# Sensor_Cheeta.net
KiCad netlist of a schematic drawn in EAGLE
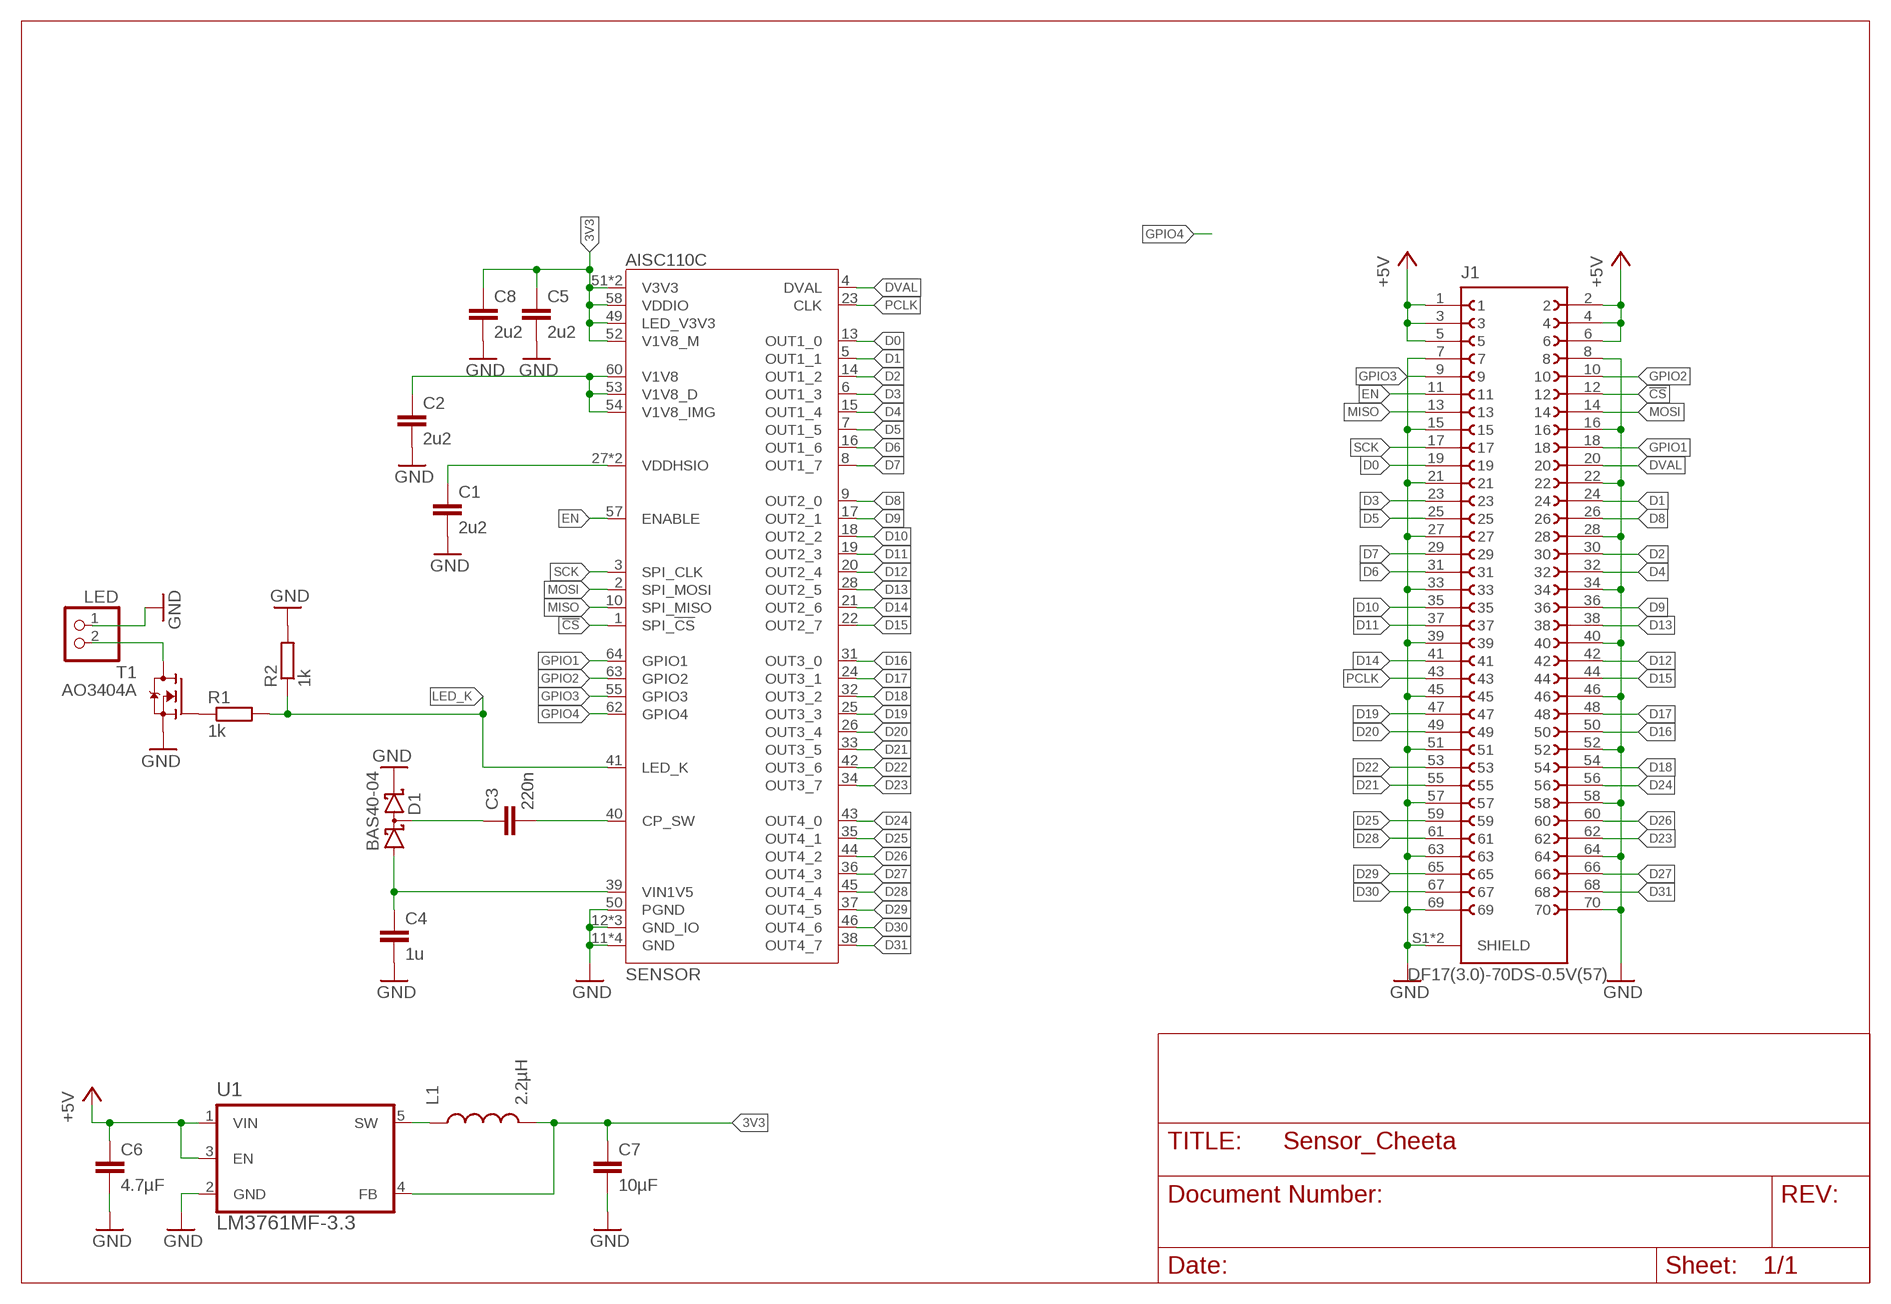
[diagram p0: schematic, sheet 1]

(export (version "E")
  (design (tool "Eeschema 10.0.6"))
  (components
    (comp (ref "C1")
      (value "2u2")
      (footprint "eagle-import:C0603")
      (libsource (lib "eagle-import") (part "rcl_334_C-EUC0603"))
    )
    (comp (ref "C2")
      (value "2u2")
      (footprint "eagle-import:C0603")
      (libsource (lib "eagle-import") (part "rcl_334_C-EUC0603"))
    )
    (comp (ref "C3")
      (value "220n")
      (footprint "eagle-import:C0603")
      (libsource (lib "eagle-import") (part "rcl_334_C-EUC0603"))
    )
    (comp (ref "C4")
      (value "1u")
      (footprint "eagle-import:C0603")
      (libsource (lib "eagle-import") (part "rcl_334_C-EUC0603"))
    )
    (comp (ref "C5")
      (value "2u2")
      (footprint "eagle-import:C0603")
      (libsource (lib "eagle-import") (part "rcl_334_C-EUC0603"))
    )
    (comp (ref "C6")
      (value "4.7µF")
      (footprint "eagle-import:C0603")
      (libsource (lib "eagle-import") (part "C-EUC0603"))
    )
    (comp (ref "C7")
      (value "10µF")
      (footprint "eagle-import:C0603")
      (libsource (lib "eagle-import") (part "C-EUC0603"))
    )
    (comp (ref "C8")
      (value "2u2")
      (footprint "eagle-import:C0603")
      (libsource (lib "eagle-import") (part "rcl_334_C-EUC0603"))
    )
    (comp (ref "D1")
      (value "BAS40-04")
      (footprint "eagle-import:SOT23")
      (libsource (lib "eagle-import") (part "BAS40-04"))
    )
    (comp (ref "J1")
      (value "DF17(3.0)-70DS-0.5V(57)")
      (footprint "eagle-import:DF17(3.0)-70DS-0.5V(57)")
      (libsource (lib "eagle-import") (part "DF17(3.0)-70DS-0.5V(57)"))
    )
    (comp (ref "L1")
      (value "2.2µH")
      (footprint "eagle-import:SO3314")
      (libsource (lib "eagle-import") (part "DO3314"))
    )
    (comp (ref "LED")
      (value "PINHD-1X2")
      (footprint "eagle-import:1X02")
      (libsource (lib "eagle-import") (part "PINHD-1X2"))
    )
    (comp (ref "R1")
      (value "1k")
      (footprint "eagle-import:R0603")
      (libsource (lib "eagle-import") (part "R-EU_R0603"))
    )
    (comp (ref "R2")
      (value "1k")
      (footprint "eagle-import:R0603")
      (libsource (lib "eagle-import") (part "R-EU_R0603"))
    )
    (comp (ref "SENSOR")
      (value "AISC110C")
      (footprint "eagle-import:64_LD_OLGA")
      (libsource (lib "eagle-import") (part "AISC110C"))
    )
    (comp (ref "T1")
      (value "AO3404A")
      (footprint "eagle-import:SOT23")
      (libsource (lib "eagle-import") (part "N-MOSFET-SOT23-3"))
    )
    (comp (ref "U1")
      (value "LM3761MF-3.3")
      (footprint "eagle-import:SOT95P284X122-5N")
      (libsource (lib "eagle-import") (part "LM3671"))
    )
  )
  (nets
    (net (code "1") (name "+5V") (class "Default")
      (node (ref "C6") (pin "1") (pinfunction "1_1") (pintype "passive"))
      (node (ref "J1") (pin "1") (pinfunction "1_1") (pintype "passive"))
      (node (ref "J1") (pin "2") (pinfunction "2_2") (pintype "passive"))
      (node (ref "J1") (pin "3") (pinfunction "3_3") (pintype "passive"))
      (node (ref "J1") (pin "4") (pinfunction "4_4") (pintype "passive"))
      (node (ref "J1") (pin "5") (pinfunction "5_5") (pintype "passive"))
      (node (ref "J1") (pin "6") (pinfunction "6_6") (pintype "passive"))
      (node (ref "U1") (pin "1") (pinfunction "VIN_1") (pintype "input"))
      (node (ref "U1") (pin "3") (pinfunction "EN_3") (pintype "passive"))
    )
    (net (code "2") (name "/~{CS}") (class "Default")
      (node (ref "J1") (pin "12") (pinfunction "12_12") (pintype "passive"))
      (node (ref "SENSOR") (pin "1") (pinfunction "SPI_~{CS}_1") (pintype "input"))
    )
    (net (code "3") (name "3V3") (class "Default")
      (node (ref "C5") (pin "1") (pinfunction "1_1") (pintype "passive"))
      (node (ref "C7") (pin "1") (pinfunction "1_1") (pintype "passive"))
      (node (ref "C8") (pin "1") (pinfunction "1_1") (pintype "passive"))
      (node (ref "L1") (pin "2") (pinfunction "2_2") (pintype "passive"))
      (node (ref "SENSOR") (pin "49") (pinfunction "LED_V3V3_49") (pintype "power_in"))
      (node (ref "SENSOR") (pin "51") (pinfunction "V3V3_51") (pintype "power_in"))
      (node (ref "SENSOR") (pin "52") (pinfunction "V1V8_M_52") (pintype "power_in"))
      (node (ref "SENSOR") (pin "58") (pinfunction "VDDIO_58") (pintype "power_in"))
      (node (ref "SENSOR") (pin "59") (pinfunction "V3V3_59") (pintype "power_in"))
      (node (ref "U1") (pin "4") (pinfunction "FB_4") (pintype "passive"))
    )
    (net (code "4") (name "D0") (class "Default")
      (node (ref "J1") (pin "19") (pinfunction "19_19") (pintype "passive"))
      (node (ref "SENSOR") (pin "13") (pinfunction "OUT1_0_13") (pintype "output"))
    )
    (net (code "5") (name "D1") (class "Default")
      (node (ref "J1") (pin "24") (pinfunction "24_24") (pintype "passive"))
      (node (ref "SENSOR") (pin "5") (pinfunction "OUT1_1_5") (pintype "output"))
    )
    (net (code "6") (name "D2") (class "Default")
      (node (ref "J1") (pin "30") (pinfunction "30_30") (pintype "passive"))
      (node (ref "SENSOR") (pin "14") (pinfunction "OUT1_2_14") (pintype "output"))
    )
    (net (code "7") (name "D3") (class "Default")
      (node (ref "J1") (pin "23") (pinfunction "23_23") (pintype "passive"))
      (node (ref "SENSOR") (pin "6") (pinfunction "OUT1_3_6") (pintype "output"))
    )
    (net (code "8") (name "D4") (class "Default")
      (node (ref "J1") (pin "32") (pinfunction "32_32") (pintype "passive"))
      (node (ref "SENSOR") (pin "15") (pinfunction "OUT1_4_15") (pintype "output"))
    )
    (net (code "9") (name "D5") (class "Default")
      (node (ref "J1") (pin "25") (pinfunction "25_25") (pintype "passive"))
      (node (ref "SENSOR") (pin "7") (pinfunction "OUT1_5_7") (pintype "output"))
    )
    (net (code "10") (name "D6") (class "Default")
      (node (ref "J1") (pin "31") (pinfunction "31_31") (pintype "passive"))
      (node (ref "SENSOR") (pin "16") (pinfunction "OUT1_6_16") (pintype "output"))
    )
    (net (code "11") (name "D7") (class "Default")
      (node (ref "J1") (pin "29") (pinfunction "29_29") (pintype "passive"))
      (node (ref "SENSOR") (pin "8") (pinfunction "OUT1_7_8") (pintype "output"))
    )
    (net (code "12") (name "D8") (class "Default")
      (node (ref "J1") (pin "26") (pinfunction "26_26") (pintype "passive"))
      (node (ref "SENSOR") (pin "9") (pinfunction "OUT2_0_9") (pintype "output"))
    )
    (net (code "13") (name "D9") (class "Default")
      (node (ref "J1") (pin "36") (pinfunction "36_36") (pintype "passive"))
      (node (ref "SENSOR") (pin "17") (pinfunction "OUT2_1_17") (pintype "output"))
    )
    (net (code "14") (name "D10") (class "Default")
      (node (ref "J1") (pin "35") (pinfunction "35_35") (pintype "passive"))
      (node (ref "SENSOR") (pin "18") (pinfunction "OUT2_2_18") (pintype "output"))
    )
    (net (code "15") (name "D11") (class "Default")
      (node (ref "J1") (pin "37") (pinfunction "37_37") (pintype "passive"))
      (node (ref "SENSOR") (pin "19") (pinfunction "OUT2_3_19") (pintype "output"))
    )
    (net (code "16") (name "D12") (class "Default")
      (node (ref "J1") (pin "42") (pinfunction "42_42") (pintype "passive"))
      (node (ref "SENSOR") (pin "20") (pinfunction "OUT2_4_20") (pintype "output"))
    )
    (net (code "17") (name "D13") (class "Default")
      (node (ref "J1") (pin "38") (pinfunction "38_38") (pintype "passive"))
      (node (ref "SENSOR") (pin "28") (pinfunction "OUT2_5_28") (pintype "output"))
    )
    (net (code "18") (name "D14") (class "Default")
      (node (ref "J1") (pin "41") (pinfunction "41_41") (pintype "passive"))
      (node (ref "SENSOR") (pin "21") (pinfunction "OUT2_6_21") (pintype "output"))
    )
    (net (code "19") (name "D15") (class "Default")
      (node (ref "J1") (pin "44") (pinfunction "44_44") (pintype "passive"))
      (node (ref "SENSOR") (pin "22") (pinfunction "OUT2_7_22") (pintype "output"))
    )
    (net (code "20") (name "D16") (class "Default")
      (node (ref "J1") (pin "50") (pinfunction "50_50") (pintype "passive"))
      (node (ref "SENSOR") (pin "31") (pinfunction "OUT3_0_31") (pintype "output"))
    )
    (net (code "21") (name "D17") (class "Default")
      (node (ref "J1") (pin "48") (pinfunction "48_48") (pintype "passive"))
      (node (ref "SENSOR") (pin "24") (pinfunction "OUT3_1_24") (pintype "output"))
    )
    (net (code "22") (name "D18") (class "Default")
      (node (ref "J1") (pin "54") (pinfunction "54_54") (pintype "passive"))
      (node (ref "SENSOR") (pin "32") (pinfunction "OUT3_2_32") (pintype "output"))
    )
    (net (code "23") (name "D19") (class "Default")
      (node (ref "J1") (pin "47") (pinfunction "47_47") (pintype "passive"))
      (node (ref "SENSOR") (pin "25") (pinfunction "OUT3_3_25") (pintype "output"))
    )
    (net (code "24") (name "D20") (class "Default")
      (node (ref "J1") (pin "49") (pinfunction "49_49") (pintype "passive"))
      (node (ref "SENSOR") (pin "26") (pinfunction "OUT3_4_26") (pintype "output"))
    )
    (net (code "25") (name "D21") (class "Default")
      (node (ref "J1") (pin "55") (pinfunction "55_55") (pintype "passive"))
      (node (ref "SENSOR") (pin "33") (pinfunction "OUT3_5_33") (pintype "output"))
    )
    (net (code "26") (name "D22") (class "Default")
      (node (ref "J1") (pin "53") (pinfunction "53_53") (pintype "passive"))
      (node (ref "SENSOR") (pin "42") (pinfunction "OUT3_6_42") (pintype "output"))
    )
    (net (code "27") (name "D23") (class "Default")
      (node (ref "J1") (pin "62") (pinfunction "62_62") (pintype "passive"))
      (node (ref "SENSOR") (pin "34") (pinfunction "OUT3_7_34") (pintype "output"))
    )
    (net (code "28") (name "D24") (class "Default")
      (node (ref "J1") (pin "56") (pinfunction "56_56") (pintype "passive"))
      (node (ref "SENSOR") (pin "43") (pinfunction "OUT4_0_43") (pintype "output"))
    )
    (net (code "29") (name "D25") (class "Default")
      (node (ref "J1") (pin "59") (pinfunction "59_59") (pintype "passive"))
      (node (ref "SENSOR") (pin "35") (pinfunction "OUT4_1_35") (pintype "output"))
    )
    (net (code "30") (name "D26") (class "Default")
      (node (ref "J1") (pin "60") (pinfunction "60_60") (pintype "passive"))
      (node (ref "SENSOR") (pin "44") (pinfunction "OUT4_2_44") (pintype "output"))
    )
    (net (code "31") (name "D27") (class "Default")
      (node (ref "J1") (pin "66") (pinfunction "66_66") (pintype "passive"))
      (node (ref "SENSOR") (pin "36") (pinfunction "OUT4_3_36") (pintype "output"))
    )
    (net (code "32") (name "D28") (class "Default")
      (node (ref "J1") (pin "61") (pinfunction "61_61") (pintype "passive"))
      (node (ref "SENSOR") (pin "45") (pinfunction "OUT4_4_45") (pintype "output"))
    )
    (net (code "33") (name "D29") (class "Default")
      (node (ref "J1") (pin "65") (pinfunction "65_65") (pintype "passive"))
      (node (ref "SENSOR") (pin "37") (pinfunction "OUT4_5_37") (pintype "output"))
    )
    (net (code "34") (name "D30") (class "Default")
      (node (ref "J1") (pin "67") (pinfunction "67_67") (pintype "passive"))
      (node (ref "SENSOR") (pin "46") (pinfunction "OUT4_6_46") (pintype "output"))
    )
    (net (code "35") (name "D31") (class "Default")
      (node (ref "J1") (pin "68") (pinfunction "68_68") (pintype "passive"))
      (node (ref "SENSOR") (pin "38") (pinfunction "OUT4_7_38") (pintype "output"))
    )
    (net (code "36") (name "DVAL") (class "Default")
      (node (ref "J1") (pin "20") (pinfunction "20_20") (pintype "passive"))
      (node (ref "SENSOR") (pin "4") (pinfunction "DVAL_4") (pintype "output"))
    )
    (net (code "37") (name "EN") (class "Default")
      (node (ref "J1") (pin "11") (pinfunction "11_11") (pintype "passive"))
      (node (ref "SENSOR") (pin "57") (pinfunction "ENABLE_57") (pintype "input"))
    )
    (net (code "38") (name "GND") (class "Default")
      (node (ref "C1") (pin "2") (pinfunction "2_2") (pintype "passive"))
      (node (ref "C2") (pin "2") (pinfunction "2_2") (pintype "passive"))
      (node (ref "C4") (pin "2") (pinfunction "2_2") (pintype "passive"))
      (node (ref "C5") (pin "2") (pinfunction "2_2") (pintype "passive"))
      (node (ref "C6") (pin "2") (pinfunction "2_2") (pintype "passive"))
      (node (ref "C7") (pin "2") (pinfunction "2_2") (pintype "passive"))
      (node (ref "C8") (pin "2") (pinfunction "2_2") (pintype "passive"))
      (node (ref "D1") (pin "2") (pinfunction "C2_2") (pintype "passive"))
      (node (ref "J1") (pin "15") (pinfunction "15_15") (pintype "passive"))
      (node (ref "J1") (pin "16") (pinfunction "16_16") (pintype "passive"))
      (node (ref "J1") (pin "21") (pinfunction "21_21") (pintype "passive"))
      (node (ref "J1") (pin "22") (pinfunction "22_22") (pintype "passive"))
      (node (ref "J1") (pin "27") (pinfunction "27_27") (pintype "passive"))
      (node (ref "J1") (pin "28") (pinfunction "28_28") (pintype "passive"))
      (node (ref "J1") (pin "33") (pinfunction "33_33") (pintype "passive"))
      (node (ref "J1") (pin "34") (pinfunction "34_34") (pintype "passive"))
      (node (ref "J1") (pin "39") (pinfunction "39_39") (pintype "passive"))
      (node (ref "J1") (pin "40") (pinfunction "40_40") (pintype "passive"))
      (node (ref "J1") (pin "45") (pinfunction "45_45") (pintype "passive"))
      (node (ref "J1") (pin "46") (pinfunction "46_46") (pintype "passive"))
      (node (ref "J1") (pin "51") (pinfunction "51_51") (pintype "passive"))
      (node (ref "J1") (pin "52") (pinfunction "52_52") (pintype "passive"))
      (node (ref "J1") (pin "57") (pinfunction "57_57") (pintype "passive"))
      (node (ref "J1") (pin "58") (pinfunction "58_58") (pintype "passive"))
      (node (ref "J1") (pin "63") (pinfunction "63_63") (pintype "passive"))
      (node (ref "J1") (pin "64") (pinfunction "64_64") (pintype "passive"))
      (node (ref "J1") (pin "69") (pinfunction "69_69") (pintype "passive"))
      (node (ref "J1") (pin "7") (pinfunction "7_7") (pintype "passive"))
      (node (ref "J1") (pin "70") (pinfunction "70_70") (pintype "passive"))
      (node (ref "J1") (pin "8") (pinfunction "8_8") (pintype "passive"))
      (node (ref "J1") (pin "S1") (pinfunction "SHIELD_S1") (pintype "passive"))
      (node (ref "J1") (pin "S2") (pinfunction "SHIELD_S2") (pintype "passive"))
      (node (ref "LED") (pin "1") (pinfunction "1_1") (pintype "passive"))
      (node (ref "R2") (pin "2") (pinfunction "2_2") (pintype "passive"))
      (node (ref "SENSOR") (pin "11") (pinfunction "GND_11") (pintype "power_in"))
      (node (ref "SENSOR") (pin "12") (pinfunction "GND_IO_12") (pintype "power_in"))
      (node (ref "SENSOR") (pin "30") (pinfunction "GND_IO_30") (pintype "power_in"))
      (node (ref "SENSOR") (pin "47") (pinfunction "GND_IO_47") (pintype "power_in"))
      (node (ref "SENSOR") (pin "48") (pinfunction "GND_48") (pintype "power_in"))
      (node (ref "SENSOR") (pin "50") (pinfunction "PGND_50") (pintype "power_in"))
      (node (ref "SENSOR") (pin "56") (pinfunction "GND_56") (pintype "power_in"))
      (node (ref "SENSOR") (pin "61") (pinfunction "GND_61") (pintype "power_in"))
      (node (ref "T1") (pin "2") (pinfunction "S_2") (pintype "passive"))
      (node (ref "U1") (pin "2") (pinfunction "GND_2") (pintype "passive"))
    )
    (net (code "39") (name "GPIO1") (class "Default")
      (node (ref "J1") (pin "18") (pinfunction "18_18") (pintype "passive"))
      (node (ref "SENSOR") (pin "64") (pinfunction "GPIO1_64") (pintype "bidirectional"))
    )
    (net (code "40") (name "GPIO2") (class "Default")
      (node (ref "J1") (pin "10") (pinfunction "10_10") (pintype "passive"))
      (node (ref "SENSOR") (pin "63") (pinfunction "GPIO2_63") (pintype "bidirectional"))
    )
    (net (code "41") (name "GPIO3") (class "Default")
      (node (ref "J1") (pin "9") (pinfunction "9_9") (pintype "passive"))
      (node (ref "SENSOR") (pin "55") (pinfunction "GPIO3_55") (pintype "bidirectional"))
    )
    (net (code "42") (name "GPIO4") (class "Default")
      (node (ref "SENSOR") (pin "62") (pinfunction "GPIO4_62") (pintype "bidirectional"))
    )
    (net (code "43") (name "LED_K") (class "Default")
      (node (ref "R1") (pin "2") (pinfunction "2_2") (pintype "passive"))
      (node (ref "R2") (pin "1") (pinfunction "1_1") (pintype "passive"))
      (node (ref "SENSOR") (pin "41") (pinfunction "LED_K_41") (pintype "passive"))
    )
    (net (code "44") (name "MISO") (class "Default")
      (node (ref "J1") (pin "13") (pinfunction "13_13") (pintype "passive"))
      (node (ref "SENSOR") (pin "10") (pinfunction "SPI_MISO_10") (pintype "output"))
    )
    (net (code "45") (name "MOSI") (class "Default")
      (node (ref "J1") (pin "14") (pinfunction "14_14") (pintype "passive"))
      (node (ref "SENSOR") (pin "2") (pinfunction "SPI_MOSI_2") (pintype "input"))
    )
    (net (code "46") (name "Net-(C1-Pad1)") (class "Default")
      (node (ref "C1") (pin "1") (pinfunction "1_1") (pintype "passive"))
      (node (ref "SENSOR") (pin "27") (pinfunction "VDDHSIO_27") (pintype "power_in"))
      (node (ref "SENSOR") (pin "29") (pinfunction "VDDHSIO_29") (pintype "power_in"))
    )
    (net (code "47") (name "Net-(D1-A1)") (class "Default")
      (node (ref "C4") (pin "1") (pinfunction "1_1") (pintype "passive"))
      (node (ref "D1") (pin "1") (pinfunction "A1_1") (pintype "passive"))
      (node (ref "SENSOR") (pin "39") (pinfunction "VIN1V5_39") (pintype "power_in"))
    )
    (net (code "48") (name "Net-(D1-C1A2)") (class "Default")
      (node (ref "C3") (pin "1") (pinfunction "1_1") (pintype "passive"))
      (node (ref "D1") (pin "3") (pinfunction "C1A2_3") (pintype "passive"))
    )
    (net (code "49") (name "Net-(SENSOR-CP_SW)") (class "Default")
      (node (ref "C3") (pin "2") (pinfunction "2_2") (pintype "passive"))
      (node (ref "SENSOR") (pin "40") (pinfunction "CP_SW_40") (pintype "output"))
    )
    (net (code "50") (name "Net-(SENSOR-V1V8)") (class "Default")
      (node (ref "C2") (pin "1") (pinfunction "1_1") (pintype "passive"))
      (node (ref "SENSOR") (pin "53") (pinfunction "V1V8_D_53") (pintype "power_in"))
      (node (ref "SENSOR") (pin "54") (pinfunction "V1V8_IMG_54") (pintype "power_in"))
      (node (ref "SENSOR") (pin "60") (pinfunction "V1V8_60") (pintype "power_in"))
    )
    (net (code "51") (name "Net-(T1-D)") (class "Default")
      (node (ref "LED") (pin "2") (pinfunction "2_2") (pintype "passive"))
      (node (ref "T1") (pin "3") (pinfunction "D_3") (pintype "passive"))
    )
    (net (code "52") (name "Net-(T1-G)") (class "Default")
      (node (ref "R1") (pin "1") (pinfunction "1_1") (pintype "passive"))
      (node (ref "T1") (pin "1") (pinfunction "G_1") (pintype "passive"))
    )
    (net (code "53") (name "Net-(U1-SW)") (class "Default")
      (node (ref "L1") (pin "1") (pinfunction "1_1") (pintype "passive"))
      (node (ref "U1") (pin "5") (pinfunction "SW_5") (pintype "output"))
    )
    (net (code "54") (name "PCLK") (class "Default")
      (node (ref "J1") (pin "43") (pinfunction "43_43") (pintype "passive"))
      (node (ref "SENSOR") (pin "23") (pinfunction "CLK_23") (pintype "output"))
    )
    (net (code "55") (name "SCK") (class "Default")
      (node (ref "J1") (pin "17") (pinfunction "17_17") (pintype "passive"))
      (node (ref "SENSOR") (pin "3") (pinfunction "SPI_CLK_3") (pintype "input"))
    )
  )
)
